# KineticMod.net
KiCad netlist of a schematic drawn in EAGLE
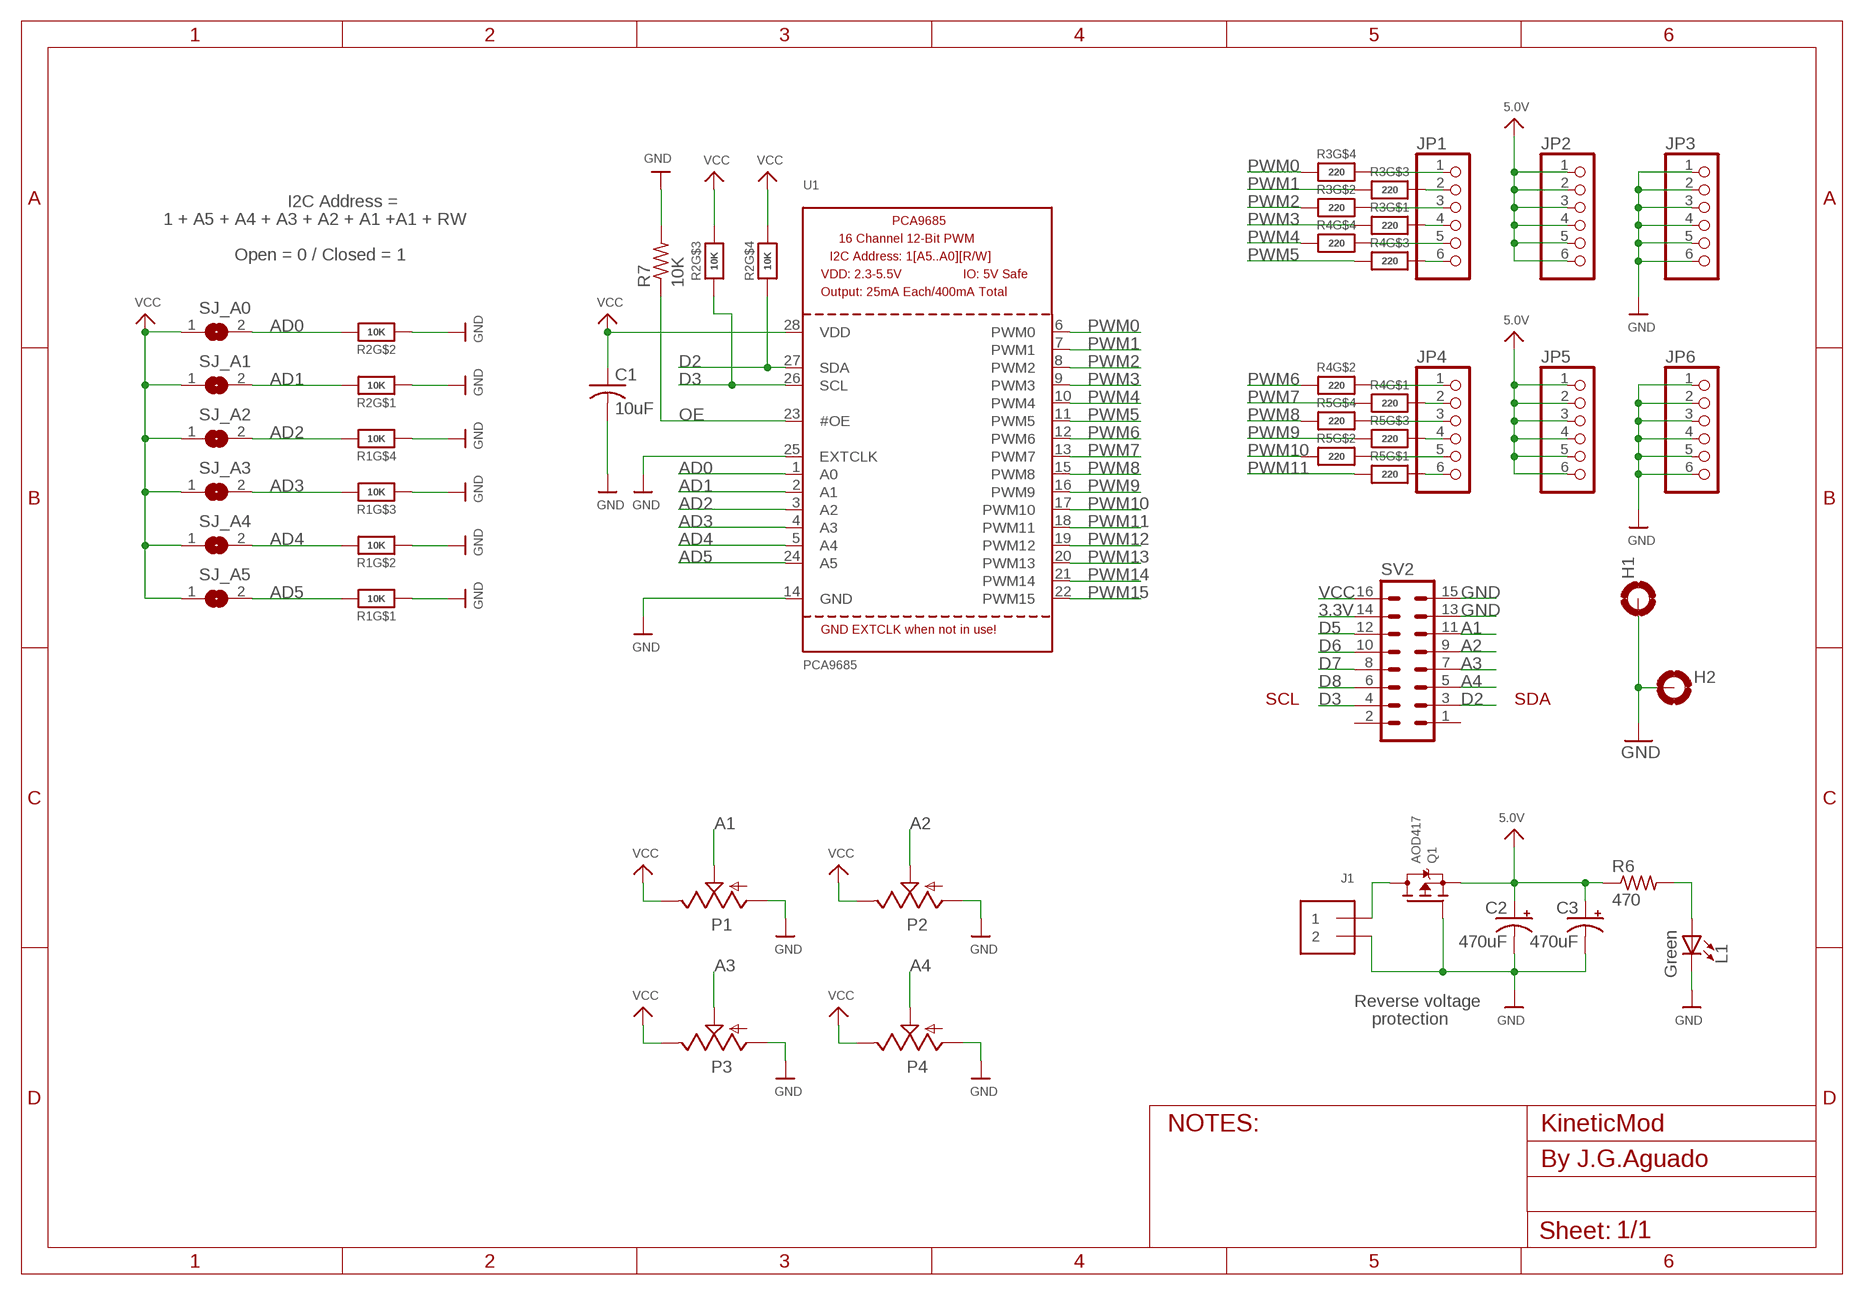
[diagram p0: schematic, sheet 1]

(export (version "E")
  (design (tool "Eeschema 10.0.6"))
  (components
    (comp (ref "C1")
      (value "10uF")
      (footprint "eagle-import:1206")
      (libsource (lib "eagle-import") (part "C1206"))
    )
    (comp (ref "C2")
      (value "470uF")
      (footprint "eagle-import:D_7343-31R")
      (libsource (lib "eagle-import") (part "CPOL-USD/7343-31R"))
    )
    (comp (ref "C3")
      (value "470uF")
      (footprint "eagle-import:D_7343-31R")
      (libsource (lib "eagle-import") (part "CPOL-USD/7343-31R"))
    )
    (comp (ref "H1")
      (value "MOUNT-PAD-ROUND3.2")
      (footprint "eagle-import:3,2-PAD")
      (libsource (lib "eagle-import") (part "MOUNT-PAD-ROUND3.2"))
    )
    (comp (ref "H2")
      (value "MOUNT-PAD-ROUND3.2")
      (footprint "eagle-import:3,2-PAD")
      (libsource (lib "eagle-import") (part "MOUNT-PAD-ROUND3.2"))
    )
    (comp (ref "J1")
      (value "TERMBLOCK_1X2")
      (footprint "eagle-import:TERMBLOCK_1X2-3.5MM")
      (libsource (lib "eagle-import") (part "TERMBLOCK_1X2"))
    )
    (comp (ref "JP1")
      (value "PINHD-1X6")
      (footprint "eagle-import:1X06")
      (libsource (lib "eagle-import") (part "PINHD-1X6"))
    )
    (comp (ref "JP2")
      (value "PINHD-1X6")
      (footprint "eagle-import:1X06")
      (libsource (lib "eagle-import") (part "PINHD-1X6"))
    )
    (comp (ref "JP3")
      (value "PINHD-1X6")
      (footprint "eagle-import:1X06")
      (libsource (lib "eagle-import") (part "PINHD-1X6"))
    )
    (comp (ref "JP4")
      (value "PINHD-1X6")
      (footprint "eagle-import:1X06")
      (libsource (lib "eagle-import") (part "PINHD-1X6"))
    )
    (comp (ref "JP5")
      (value "PINHD-1X6")
      (footprint "eagle-import:1X06")
      (libsource (lib "eagle-import") (part "PINHD-1X6"))
    )
    (comp (ref "JP6")
      (value "PINHD-1X6")
      (footprint "eagle-import:1X06")
      (libsource (lib "eagle-import") (part "PINHD-1X6"))
    )
    (comp (ref "L1")
      (value "Green")
      (footprint "eagle-import:LED1206")
      (libsource (lib "eagle-import") (part "LED1206"))
    )
    (comp (ref "P1")
      (value "ALPS_RK09K_VERTICAL")
      (footprint "eagle-import:ALPS_RK09K_VERTICAL")
      (libsource (lib "eagle-import") (part "ALPS_RK09K_VERTICAL"))
    )
    (comp (ref "P2")
      (value "ALPS_RK09K_VERTICAL")
      (footprint "eagle-import:ALPS_RK09K_VERTICAL")
      (libsource (lib "eagle-import") (part "ALPS_RK09K_VERTICAL"))
    )
    (comp (ref "P3")
      (value "ALPS_RK09K_VERTICAL")
      (footprint "eagle-import:ALPS_RK09K_VERTICAL")
      (libsource (lib "eagle-import") (part "ALPS_RK09K_VERTICAL"))
    )
    (comp (ref "P4")
      (value "ALPS_RK09K_VERTICAL")
      (footprint "eagle-import:ALPS_RK09K_VERTICAL")
      (libsource (lib "eagle-import") (part "ALPS_RK09K_VERTICAL"))
    )
    (comp (ref "Q1")
      (value "AOD417")
      (footprint "eagle-import:TO252")
      (libsource (lib "eagle-import") (part "MOSFET-PTO252"))
    )
    (comp (ref "R1")
      (value "10K")
      (footprint "eagle-import:RESPACK_4X0603")
      (libsource (lib "eagle-import") (part "RESISTOR_4PACK"))
    )
    (comp (ref "R2")
      (value "10K")
      (footprint "eagle-import:RESPACK_4X0603")
      (libsource (lib "eagle-import") (part "RESISTOR_4PACK"))
    )
    (comp (ref "R3")
      (value "220")
      (footprint "eagle-import:RESPACK_4X0603")
      (libsource (lib "eagle-import") (part "RESISTOR_4PACK"))
    )
    (comp (ref "R4")
      (value "220")
      (footprint "eagle-import:RESPACK_4X0603")
      (libsource (lib "eagle-import") (part "RESISTOR_4PACK"))
    )
    (comp (ref "R5")
      (value "220")
      (footprint "eagle-import:RESPACK_4X0603")
      (libsource (lib "eagle-import") (part "RESISTOR_4PACK"))
    )
    (comp (ref "R6")
      (value "470")
      (footprint "eagle-import:1206")
      (libsource (lib "eagle-import") (part "R1206"))
    )
    (comp (ref "R7")
      (value "10K")
      (footprint "eagle-import:1206")
      (libsource (lib "eagle-import") (part "R1206"))
    )
    (comp (ref "SJ_A0")
      (value "SOLDERJUMPERREFLOW_NOPASTE")
      (footprint "eagle-import:SOLDERJUMPER_REFLOW_NOPASTE")
      (libsource (lib "eagle-import") (part "SOLDERJUMPERREFLOW_NOPASTE"))
    )
    (comp (ref "SJ_A1")
      (value "SOLDERJUMPERREFLOW_NOPASTE")
      (footprint "eagle-import:SOLDERJUMPER_REFLOW_NOPASTE")
      (libsource (lib "eagle-import") (part "SOLDERJUMPERREFLOW_NOPASTE"))
    )
    (comp (ref "SJ_A2")
      (value "SOLDERJUMPERREFLOW_NOPASTE")
      (footprint "eagle-import:SOLDERJUMPER_REFLOW_NOPASTE")
      (libsource (lib "eagle-import") (part "SOLDERJUMPERREFLOW_NOPASTE"))
    )
    (comp (ref "SJ_A3")
      (value "SOLDERJUMPERREFLOW_NOPASTE")
      (footprint "eagle-import:SOLDERJUMPER_REFLOW_NOPASTE")
      (libsource (lib "eagle-import") (part "SOLDERJUMPERREFLOW_NOPASTE"))
    )
    (comp (ref "SJ_A4")
      (value "SOLDERJUMPERREFLOW_NOPASTE")
      (footprint "eagle-import:SOLDERJUMPER_REFLOW_NOPASTE")
      (libsource (lib "eagle-import") (part "SOLDERJUMPERREFLOW_NOPASTE"))
    )
    (comp (ref "SJ_A5")
      (value "SOLDERJUMPERREFLOW_NOPASTE")
      (footprint "eagle-import:SOLDERJUMPER_REFLOW_NOPASTE")
      (libsource (lib "eagle-import") (part "SOLDERJUMPERREFLOW_NOPASTE"))
    )
    (comp (ref "SV2")
      (value "MA08-2")
      (footprint "eagle-import:MA08-2")
      (libsource (lib "eagle-import") (part "MA08-2"))
    )
    (comp (ref "U1")
      (value "PCA9685")
      (footprint "eagle-import:TSSOP28")
      (libsource (lib "eagle-import") (part "PCA9685"))
    )
  )
  (nets
    (net (code "1") (name "/3.3V") (class "Default")
      (node (ref "SV2") (pin "14") (pinfunction "14_14") (pintype "passive"))
    )
    (net (code "2") (name "/A1") (class "Default")
      (node (ref "P1") (pin "2") (pinfunction "2_2") (pintype "passive"))
      (node (ref "SV2") (pin "11") (pinfunction "11_11") (pintype "passive"))
    )
    (net (code "3") (name "/A2") (class "Default")
      (node (ref "P2") (pin "2") (pinfunction "2_2") (pintype "passive"))
      (node (ref "SV2") (pin "9") (pinfunction "9_9") (pintype "passive"))
    )
    (net (code "4") (name "/A3") (class "Default")
      (node (ref "P3") (pin "2") (pinfunction "2_2") (pintype "passive"))
      (node (ref "SV2") (pin "7") (pinfunction "7_7") (pintype "passive"))
    )
    (net (code "5") (name "/A4") (class "Default")
      (node (ref "P4") (pin "2") (pinfunction "2_2") (pintype "passive"))
      (node (ref "SV2") (pin "5") (pinfunction "5_5") (pintype "passive"))
    )
    (net (code "6") (name "/AD0") (class "Default")
      (node (ref "R2") (pin "7") (pinfunction "2_7") (pintype "passive"))
      (node (ref "SJ_A0") (pin "2") (pinfunction "2_2") (pintype "passive"))
      (node (ref "U1") (pin "1") (pinfunction "A0_1") (pintype "bidirectional"))
    )
    (net (code "7") (name "/AD1") (class "Default")
      (node (ref "R2") (pin "8") (pinfunction "2_8") (pintype "passive"))
      (node (ref "SJ_A1") (pin "2") (pinfunction "2_2") (pintype "passive"))
      (node (ref "U1") (pin "2") (pinfunction "A1_2") (pintype "bidirectional"))
    )
    (net (code "8") (name "/AD2") (class "Default")
      (node (ref "R1") (pin "5") (pinfunction "2_5") (pintype "passive"))
      (node (ref "SJ_A2") (pin "2") (pinfunction "2_2") (pintype "passive"))
      (node (ref "U1") (pin "3") (pinfunction "A2_3") (pintype "bidirectional"))
    )
    (net (code "9") (name "/AD3") (class "Default")
      (node (ref "R1") (pin "6") (pinfunction "2_6") (pintype "passive"))
      (node (ref "SJ_A3") (pin "2") (pinfunction "2_2") (pintype "passive"))
      (node (ref "U1") (pin "4") (pinfunction "A3_4") (pintype "bidirectional"))
    )
    (net (code "10") (name "/AD4") (class "Default")
      (node (ref "R1") (pin "7") (pinfunction "2_7") (pintype "passive"))
      (node (ref "SJ_A4") (pin "2") (pinfunction "2_2") (pintype "passive"))
      (node (ref "U1") (pin "5") (pinfunction "A4_5") (pintype "bidirectional"))
    )
    (net (code "11") (name "/AD5") (class "Default")
      (node (ref "R1") (pin "8") (pinfunction "2_8") (pintype "passive"))
      (node (ref "SJ_A5") (pin "2") (pinfunction "2_2") (pintype "passive"))
      (node (ref "U1") (pin "24") (pinfunction "A5_24") (pintype "bidirectional"))
    )
    (net (code "12") (name "/D2") (class "Default")
      (node (ref "R2") (pin "4") (pinfunction "1_4") (pintype "passive"))
      (node (ref "SV2") (pin "3") (pinfunction "3_3") (pintype "passive"))
      (node (ref "U1") (pin "27") (pinfunction "SDA_27") (pintype "bidirectional"))
    )
    (net (code "13") (name "/D3") (class "Default")
      (node (ref "R2") (pin "3") (pinfunction "1_3") (pintype "passive"))
      (node (ref "SV2") (pin "4") (pinfunction "4_4") (pintype "passive"))
      (node (ref "U1") (pin "26") (pinfunction "SCL_26") (pintype "bidirectional"))
    )
    (net (code "14") (name "/D5") (class "Default")
      (node (ref "SV2") (pin "12") (pinfunction "12_12") (pintype "passive"))
    )
    (net (code "15") (name "/D6") (class "Default")
      (node (ref "SV2") (pin "10") (pinfunction "10_10") (pintype "passive"))
    )
    (net (code "16") (name "/D7") (class "Default")
      (node (ref "SV2") (pin "8") (pinfunction "8_8") (pintype "passive"))
    )
    (net (code "17") (name "/D8") (class "Default")
      (node (ref "SV2") (pin "6") (pinfunction "6_6") (pintype "passive"))
    )
    (net (code "18") (name "/OE") (class "Default")
      (node (ref "R7") (pin "1") (pinfunction "1_1") (pintype "passive"))
      (node (ref "U1") (pin "23") (pinfunction "#OE_23") (pintype "input"))
    )
    (net (code "19") (name "/PWM0") (class "Default")
      (node (ref "R3") (pin "4") (pinfunction "1_4") (pintype "passive"))
      (node (ref "U1") (pin "6") (pinfunction "PWM0_6") (pintype "output"))
    )
    (net (code "20") (name "/PWM1") (class "Default")
      (node (ref "R3") (pin "3") (pinfunction "1_3") (pintype "passive"))
      (node (ref "U1") (pin "7") (pinfunction "PWM1_7") (pintype "output"))
    )
    (net (code "21") (name "/PWM2") (class "Default")
      (node (ref "R3") (pin "2") (pinfunction "1_2") (pintype "passive"))
      (node (ref "U1") (pin "8") (pinfunction "PWM2_8") (pintype "output"))
    )
    (net (code "22") (name "/PWM3") (class "Default")
      (node (ref "R3") (pin "1") (pinfunction "1_1") (pintype "passive"))
      (node (ref "U1") (pin "9") (pinfunction "PWM3_9") (pintype "output"))
    )
    (net (code "23") (name "/PWM4") (class "Default")
      (node (ref "R4") (pin "4") (pinfunction "1_4") (pintype "passive"))
      (node (ref "U1") (pin "10") (pinfunction "PWM4_10") (pintype "output"))
    )
    (net (code "24") (name "/PWM5") (class "Default")
      (node (ref "R4") (pin "3") (pinfunction "1_3") (pintype "passive"))
      (node (ref "U1") (pin "11") (pinfunction "PWM5_11") (pintype "output"))
    )
    (net (code "25") (name "/PWM6") (class "Default")
      (node (ref "R4") (pin "2") (pinfunction "1_2") (pintype "passive"))
      (node (ref "U1") (pin "12") (pinfunction "PWM6_12") (pintype "output"))
    )
    (net (code "26") (name "/PWM7") (class "Default")
      (node (ref "R4") (pin "1") (pinfunction "1_1") (pintype "passive"))
      (node (ref "U1") (pin "13") (pinfunction "PWM7_13") (pintype "output"))
    )
    (net (code "27") (name "/PWM8") (class "Default")
      (node (ref "R5") (pin "4") (pinfunction "1_4") (pintype "passive"))
      (node (ref "U1") (pin "15") (pinfunction "PWM8_15") (pintype "output"))
    )
    (net (code "28") (name "/PWM9") (class "Default")
      (node (ref "R5") (pin "3") (pinfunction "1_3") (pintype "passive"))
      (node (ref "U1") (pin "16") (pinfunction "PWM9_16") (pintype "output"))
    )
    (net (code "29") (name "/PWM10") (class "Default")
      (node (ref "R5") (pin "2") (pinfunction "1_2") (pintype "passive"))
      (node (ref "U1") (pin "17") (pinfunction "PWM10_17") (pintype "output"))
    )
    (net (code "30") (name "/PWM11") (class "Default")
      (node (ref "R5") (pin "1") (pinfunction "1_1") (pintype "passive"))
      (node (ref "U1") (pin "18") (pinfunction "PWM11_18") (pintype "output"))
    )
    (net (code "31") (name "/PWM12") (class "Default")
      (node (ref "U1") (pin "19") (pinfunction "PWM12_19") (pintype "output"))
    )
    (net (code "32") (name "/PWM13") (class "Default")
      (node (ref "U1") (pin "20") (pinfunction "PWM13_20") (pintype "output"))
    )
    (net (code "33") (name "/PWM14") (class "Default")
      (node (ref "U1") (pin "21") (pinfunction "PWM14_21") (pintype "output"))
    )
    (net (code "34") (name "/PWM15") (class "Default")
      (node (ref "U1") (pin "22") (pinfunction "PWM15_22") (pintype "output"))
    )
    (net (code "35") (name "5.0V") (class "Default")
      (node (ref "C2") (pin "+") (pinfunction "+_+") (pintype "passive"))
      (node (ref "C3") (pin "+") (pinfunction "+_+") (pintype "passive"))
      (node (ref "JP2") (pin "1") (pinfunction "1_1") (pintype "passive"))
      (node (ref "JP2") (pin "2") (pinfunction "2_2") (pintype "passive"))
      (node (ref "JP2") (pin "3") (pinfunction "3_3") (pintype "passive"))
      (node (ref "JP2") (pin "4") (pinfunction "4_4") (pintype "passive"))
      (node (ref "JP2") (pin "5") (pinfunction "5_5") (pintype "passive"))
      (node (ref "JP2") (pin "6") (pinfunction "6_6") (pintype "passive"))
      (node (ref "JP5") (pin "1") (pinfunction "1_1") (pintype "passive"))
      (node (ref "JP5") (pin "2") (pinfunction "2_2") (pintype "passive"))
      (node (ref "JP5") (pin "3") (pinfunction "3_3") (pintype "passive"))
      (node (ref "JP5") (pin "4") (pinfunction "4_4") (pintype "passive"))
      (node (ref "JP5") (pin "5") (pinfunction "5_5") (pintype "passive"))
      (node (ref "JP5") (pin "6") (pinfunction "6_6") (pintype "passive"))
      (node (ref "Q1") (pin "2") (pinfunction "S_2") (pintype "passive"))
      (node (ref "R6") (pin "1") (pinfunction "1_1") (pintype "passive"))
    )
    (net (code "36") (name "GND") (class "Default")
      (node (ref "C1") (pin "2") (pinfunction "2_2") (pintype "passive"))
      (node (ref "C2") (pin "-") (pinfunction "-_-") (pintype "passive"))
      (node (ref "C3") (pin "-") (pinfunction "-_-") (pintype "passive"))
      (node (ref "H1") (pin "B3,2") (pinfunction "MOUNT_B3,2") (pintype "passive"))
      (node (ref "H2") (pin "B3,2") (pinfunction "MOUNT_B3,2") (pintype "passive"))
      (node (ref "J1") (pin "2") (pinfunction "2_2") (pintype "passive"))
      (node (ref "JP3") (pin "1") (pinfunction "1_1") (pintype "passive"))
      (node (ref "JP3") (pin "2") (pinfunction "2_2") (pintype "passive"))
      (node (ref "JP3") (pin "3") (pinfunction "3_3") (pintype "passive"))
      (node (ref "JP3") (pin "4") (pinfunction "4_4") (pintype "passive"))
      (node (ref "JP3") (pin "5") (pinfunction "5_5") (pintype "passive"))
      (node (ref "JP3") (pin "6") (pinfunction "6_6") (pintype "passive"))
      (node (ref "JP6") (pin "1") (pinfunction "1_1") (pintype "passive"))
      (node (ref "JP6") (pin "2") (pinfunction "2_2") (pintype "passive"))
      (node (ref "JP6") (pin "3") (pinfunction "3_3") (pintype "passive"))
      (node (ref "JP6") (pin "4") (pinfunction "4_4") (pintype "passive"))
      (node (ref "JP6") (pin "5") (pinfunction "5_5") (pintype "passive"))
      (node (ref "JP6") (pin "6") (pinfunction "6_6") (pintype "passive"))
      (node (ref "L1") (pin "C") (pinfunction "C_C") (pintype "passive"))
      (node (ref "P1") (pin "1") (pinfunction "1_1") (pintype "passive"))
      (node (ref "P2") (pin "1") (pinfunction "1_1") (pintype "passive"))
      (node (ref "P3") (pin "1") (pinfunction "1_1") (pintype "passive"))
      (node (ref "P4") (pin "1") (pinfunction "1_1") (pintype "passive"))
      (node (ref "Q1") (pin "1") (pinfunction "G_1") (pintype "passive"))
      (node (ref "R1") (pin "1") (pinfunction "1_1") (pintype "passive"))
      (node (ref "R1") (pin "2") (pinfunction "1_2") (pintype "passive"))
      (node (ref "R1") (pin "3") (pinfunction "1_3") (pintype "passive"))
      (node (ref "R1") (pin "4") (pinfunction "1_4") (pintype "passive"))
      (node (ref "R2") (pin "1") (pinfunction "1_1") (pintype "passive"))
      (node (ref "R2") (pin "2") (pinfunction "1_2") (pintype "passive"))
      (node (ref "R7") (pin "2") (pinfunction "2_2") (pintype "passive"))
      (node (ref "SV2") (pin "13") (pinfunction "13_13") (pintype "passive"))
      (node (ref "SV2") (pin "15") (pinfunction "15_15") (pintype "passive"))
      (node (ref "U1") (pin "14") (pinfunction "GND_14") (pintype "power_in"))
      (node (ref "U1") (pin "25") (pinfunction "EXTCLK_25") (pintype "input"))
    )
    (net (code "37") (name "Net-(L1-PadA)") (class "Default")
      (node (ref "L1") (pin "A") (pinfunction "A_A") (pintype "passive"))
      (node (ref "R6") (pin "2") (pinfunction "2_2") (pintype "passive"))
    )
    (net (code "38") (name "Net-(Q1-D)") (class "Default")
      (node (ref "J1") (pin "1") (pinfunction "1_1") (pintype "passive"))
      (node (ref "Q1") (pin "3") (pinfunction "D_3") (pintype "passive"))
    )
    (net (code "39") (name "Net-(R3A-2)") (class "Default")
      (node (ref "JP1") (pin "4") (pinfunction "4_4") (pintype "passive"))
      (node (ref "R3") (pin "8") (pinfunction "2_8") (pintype "passive"))
    )
    (net (code "40") (name "Net-(R3B-2)") (class "Default")
      (node (ref "JP1") (pin "3") (pinfunction "3_3") (pintype "passive"))
      (node (ref "R3") (pin "7") (pinfunction "2_7") (pintype "passive"))
    )
    (net (code "41") (name "Net-(R3C-2)") (class "Default")
      (node (ref "JP1") (pin "2") (pinfunction "2_2") (pintype "passive"))
      (node (ref "R3") (pin "6") (pinfunction "2_6") (pintype "passive"))
    )
    (net (code "42") (name "Net-(R3D-2)") (class "Default")
      (node (ref "JP1") (pin "1") (pinfunction "1_1") (pintype "passive"))
      (node (ref "R3") (pin "5") (pinfunction "2_5") (pintype "passive"))
    )
    (net (code "43") (name "Net-(R4A-2)") (class "Default")
      (node (ref "JP4") (pin "2") (pinfunction "2_2") (pintype "passive"))
      (node (ref "R4") (pin "8") (pinfunction "2_8") (pintype "passive"))
    )
    (net (code "44") (name "Net-(R4B-2)") (class "Default")
      (node (ref "JP4") (pin "1") (pinfunction "1_1") (pintype "passive"))
      (node (ref "R4") (pin "7") (pinfunction "2_7") (pintype "passive"))
    )
    (net (code "45") (name "Net-(R4C-2)") (class "Default")
      (node (ref "JP1") (pin "6") (pinfunction "6_6") (pintype "passive"))
      (node (ref "R4") (pin "6") (pinfunction "2_6") (pintype "passive"))
    )
    (net (code "46") (name "Net-(R4D-2)") (class "Default")
      (node (ref "JP1") (pin "5") (pinfunction "5_5") (pintype "passive"))
      (node (ref "R4") (pin "5") (pinfunction "2_5") (pintype "passive"))
    )
    (net (code "47") (name "Net-(R5A-2)") (class "Default")
      (node (ref "JP4") (pin "6") (pinfunction "6_6") (pintype "passive"))
      (node (ref "R5") (pin "8") (pinfunction "2_8") (pintype "passive"))
    )
    (net (code "48") (name "Net-(R5B-2)") (class "Default")
      (node (ref "JP4") (pin "5") (pinfunction "5_5") (pintype "passive"))
      (node (ref "R5") (pin "7") (pinfunction "2_7") (pintype "passive"))
    )
    (net (code "49") (name "Net-(R5C-2)") (class "Default")
      (node (ref "JP4") (pin "4") (pinfunction "4_4") (pintype "passive"))
      (node (ref "R5") (pin "6") (pinfunction "2_6") (pintype "passive"))
    )
    (net (code "50") (name "Net-(R5D-2)") (class "Default")
      (node (ref "JP4") (pin "3") (pinfunction "3_3") (pintype "passive"))
      (node (ref "R5") (pin "5") (pinfunction "2_5") (pintype "passive"))
    )
    (net (code "51") (name "VCC") (class "Default")
      (node (ref "C1") (pin "1") (pinfunction "1_1") (pintype "passive"))
      (node (ref "P1") (pin "3") (pinfunction "3_3") (pintype "passive"))
      (node (ref "P2") (pin "3") (pinfunction "3_3") (pintype "passive"))
      (node (ref "P3") (pin "3") (pinfunction "3_3") (pintype "passive"))
      (node (ref "P4") (pin "3") (pinfunction "3_3") (pintype "passive"))
      (node (ref "R2") (pin "5") (pinfunction "2_5") (pintype "passive"))
      (node (ref "R2") (pin "6") (pinfunction "2_6") (pintype "passive"))
      (node (ref "SJ_A0") (pin "1") (pinfunction "1_1") (pintype "passive"))
      (node (ref "SJ_A1") (pin "1") (pinfunction "1_1") (pintype "passive"))
      (node (ref "SJ_A2") (pin "1") (pinfunction "1_1") (pintype "passive"))
      (node (ref "SJ_A3") (pin "1") (pinfunction "1_1") (pintype "passive"))
      (node (ref "SJ_A4") (pin "1") (pinfunction "1_1") (pintype "passive"))
      (node (ref "SJ_A5") (pin "1") (pinfunction "1_1") (pintype "passive"))
      (node (ref "SV2") (pin "16") (pinfunction "16_16") (pintype "passive"))
      (node (ref "U1") (pin "28") (pinfunction "VDD_28") (pintype "power_in"))
    )
    (net (code "52") (name "unconnected-(SV2-Pad1)") (class "Default")
      (node (ref "SV2") (pin "1") (pinfunction "1_1") (pintype "passive"))
    )
    (net (code "53") (name "unconnected-(SV2-Pad2)") (class "Default")
      (node (ref "SV2") (pin "2") (pinfunction "2_2") (pintype "passive"))
    )
  )
)
